# ECG_BTLE.net
KiCad netlist of a schematic drawn in EAGLE
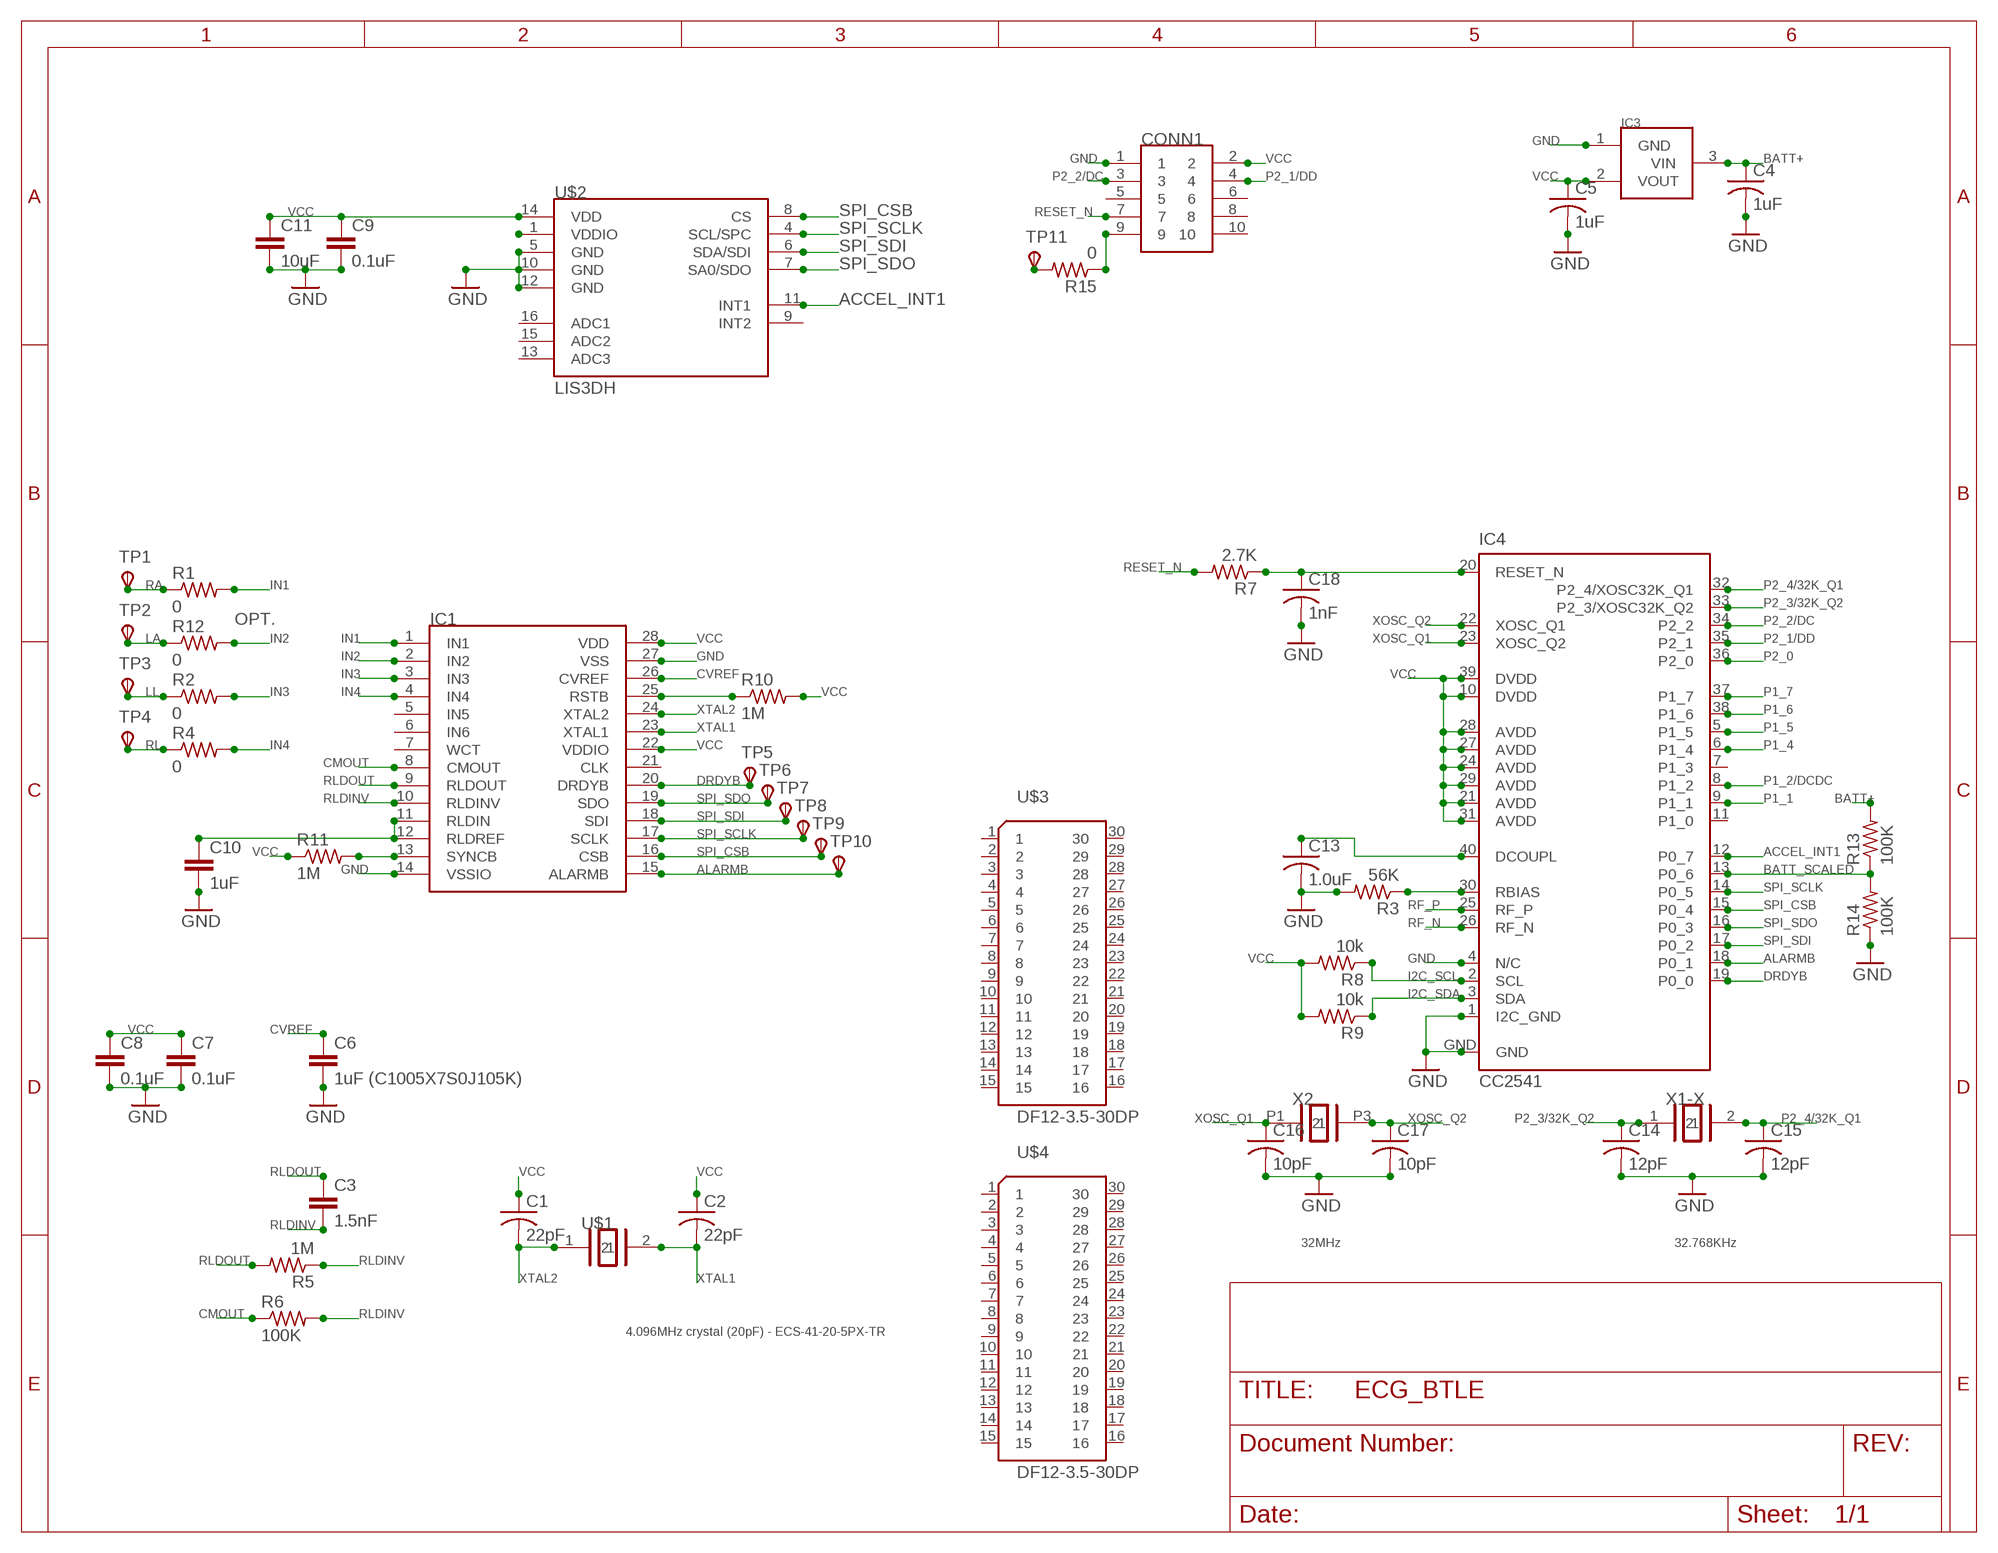
[diagram p0: schematic, sheet 1]

(export (version "E")
  (design (tool "Eeschema 10.0.6"))
  (components
    (comp (ref "C1")
      (value "22pF")
      (footprint "eagle-import:C0201")
      (libsource (lib "eagle-import") (part "C-USC0201"))
    )
    (comp (ref "C2")
      (value "22pF")
      (footprint "eagle-import:C0201")
      (libsource (lib "eagle-import") (part "C-USC0201"))
    )
    (comp (ref "C3")
      (value "1.5nF")
      (footprint "eagle-import:C0402")
      (libsource (lib "eagle-import") (part "C-EUC0402"))
    )
    (comp (ref "C4")
      (value "1uF")
      (footprint "eagle-import:C0201")
      (libsource (lib "eagle-import") (part "C-USC0201"))
    )
    (comp (ref "C5")
      (value "1uF")
      (footprint "eagle-import:C0201")
      (libsource (lib "eagle-import") (part "C-USC0201"))
    )
    (comp (ref "C6")
      (value "1uF (C1005X7S0J105K)")
      (footprint "eagle-import:C0402")
      (libsource (lib "eagle-import") (part "C-EUC0402"))
    )
    (comp (ref "C7")
      (value "0.1uF")
      (footprint "eagle-import:C0402")
      (libsource (lib "eagle-import") (part "C-EUC0402"))
    )
    (comp (ref "C8")
      (value "0.1uF")
      (footprint "eagle-import:C0402")
      (libsource (lib "eagle-import") (part "C-EUC0402"))
    )
    (comp (ref "C9")
      (value "0.1uF")
      (footprint "eagle-import:C0402")
      (libsource (lib "eagle-import") (part "C-EUC0402"))
    )
    (comp (ref "C10")
      (value "1uF")
      (footprint "eagle-import:C0402")
      (libsource (lib "eagle-import") (part "C-EUC0402"))
    )
    (comp (ref "C11")
      (value "10uF")
      (footprint "eagle-import:C0402")
      (libsource (lib "eagle-import") (part "C-EUC0402"))
    )
    (comp (ref "C13")
      (value "1.0uF")
      (footprint "eagle-import:C0402")
      (libsource (lib "eagle-import") (part "C-USC0402"))
    )
    (comp (ref "C14")
      (value "12pF")
      (footprint "eagle-import:C0201")
      (libsource (lib "eagle-import") (part "C-USC0201"))
    )
    (comp (ref "C15")
      (value "12pF")
      (footprint "eagle-import:C0201")
      (libsource (lib "eagle-import") (part "C-USC0201"))
    )
    (comp (ref "C16")
      (value "10pF")
      (footprint "eagle-import:C0201")
      (libsource (lib "eagle-import") (part "C-USC0201"))
    )
    (comp (ref "C17")
      (value "10pF")
      (footprint "eagle-import:C0201")
      (libsource (lib "eagle-import") (part "C-USC0201"))
    )
    (comp (ref "C18")
      (value "1nF")
      (footprint "eagle-import:C0402")
      (libsource (lib "eagle-import") (part "C-USC0402"))
    )
    (comp (ref "CONN1")
      (value "10POS_1.27MM_SMD")
      (footprint "eagle-import:1.27MM_SMD")
      (libsource (lib "eagle-import") (part "10POS_1.27MM_SMD"))
    )
    (comp (ref "IC1")
      (value "ADS1293")
      (footprint "eagle-import:WQFN28")
      (libsource (lib "eagle-import") (part "ADS1293"))
    )
    (comp (ref "IC3")
      (value "MCP1703")
      (footprint "eagle-import:SOT23")
      (libsource (lib "eagle-import") (part "MCP1703"))
    )
    (comp (ref "IC4")
      (value "CC2541")
      (footprint "eagle-import:RHA_S-PVQFN-N40")
      (libsource (lib "eagle-import") (part "CC2541"))
    )
    (comp (ref "R1")
      (value "0")
      (footprint "eagle-import:R0402")
      (libsource (lib "eagle-import") (part "resistor_R-US_R0402"))
    )
    (comp (ref "R2")
      (value "0")
      (footprint "eagle-import:R0402")
      (libsource (lib "eagle-import") (part "resistor_R-US_R0402"))
    )
    (comp (ref "R3")
      (value "56K")
      (footprint "eagle-import:R0201")
      (libsource (lib "eagle-import") (part "R-US_R0201"))
    )
    (comp (ref "R4")
      (value "0")
      (footprint "eagle-import:R0402")
      (libsource (lib "eagle-import") (part "resistor_R-US_R0402"))
    )
    (comp (ref "R5")
      (value "1M")
      (footprint "eagle-import:R0603")
      (libsource (lib "eagle-import") (part "resistor_R-US_R0603"))
    )
    (comp (ref "R6")
      (value "100K")
      (footprint "eagle-import:R0402")
      (libsource (lib "eagle-import") (part "resistor_R-US_R0402"))
    )
    (comp (ref "R7")
      (value "2.7K")
      (footprint "eagle-import:R0201")
      (libsource (lib "eagle-import") (part "R-US_R0201"))
    )
    (comp (ref "R8")
      (value "10k")
      (footprint "eagle-import:R0201")
      (libsource (lib "eagle-import") (part "R-US_R0201"))
    )
    (comp (ref "R9")
      (value "10k")
      (footprint "eagle-import:R0201")
      (libsource (lib "eagle-import") (part "R-US_R0201"))
    )
    (comp (ref "R10")
      (value "1M")
      (footprint "eagle-import:R0402")
      (libsource (lib "eagle-import") (part "resistor_R-US_R0402"))
    )
    (comp (ref "R11")
      (value "1M")
      (footprint "eagle-import:R0402")
      (libsource (lib "eagle-import") (part "resistor_R-US_R0402"))
    )
    (comp (ref "R12")
      (value "0")
      (footprint "eagle-import:R0402")
      (libsource (lib "eagle-import") (part "resistor_R-US_R0402"))
    )
    (comp (ref "R13")
      (value "100K")
      (footprint "eagle-import:R0201")
      (libsource (lib "eagle-import") (part "R-US_R0201"))
    )
    (comp (ref "R14")
      (value "100K")
      (footprint "eagle-import:R0201")
      (libsource (lib "eagle-import") (part "R-US_R0201"))
    )
    (comp (ref "R15")
      (value "0")
      (footprint "eagle-import:R0201")
      (libsource (lib "eagle-import") (part "R-US_R0201"))
    )
    (comp (ref "TP1")
      (value "TPSTP08SQ")
      (footprint "eagle-import:TP08SQ")
      (libsource (lib "eagle-import") (part "TPSTP08SQ"))
    )
    (comp (ref "TP2")
      (value "TPSTP08SQ")
      (footprint "eagle-import:TP08SQ")
      (libsource (lib "eagle-import") (part "TPSTP08SQ"))
    )
    (comp (ref "TP3")
      (value "TPSTP08SQ")
      (footprint "eagle-import:TP08SQ")
      (libsource (lib "eagle-import") (part "TPSTP08SQ"))
    )
    (comp (ref "TP4")
      (value "TPSTP08SQ")
      (footprint "eagle-import:TP08SQ")
      (libsource (lib "eagle-import") (part "TPSTP08SQ"))
    )
    (comp (ref "TP5")
      (value "TPSTP08SQ")
      (footprint "eagle-import:TP08SQ")
      (libsource (lib "eagle-import") (part "TPSTP08SQ"))
    )
    (comp (ref "TP6")
      (value "TPSTP08SQ")
      (footprint "eagle-import:TP08SQ")
      (libsource (lib "eagle-import") (part "TPSTP08SQ"))
    )
    (comp (ref "TP7")
      (value "TPSTP08SQ")
      (footprint "eagle-import:TP08SQ")
      (libsource (lib "eagle-import") (part "TPSTP08SQ"))
    )
    (comp (ref "TP8")
      (value "TPSTP08SQ")
      (footprint "eagle-import:TP08SQ")
      (libsource (lib "eagle-import") (part "TPSTP08SQ"))
    )
    (comp (ref "TP9")
      (value "TPSTP08SQ")
      (footprint "eagle-import:TP08SQ")
      (libsource (lib "eagle-import") (part "TPSTP08SQ"))
    )
    (comp (ref "TP10")
      (value "TPSTP08SQ")
      (footprint "eagle-import:TP08SQ")
      (libsource (lib "eagle-import") (part "TPSTP08SQ"))
    )
    (comp (ref "TP11")
      (value "TPSTP08SQ")
      (footprint "eagle-import:TP08SQ")
      (libsource (lib "eagle-import") (part "TPSTP08SQ"))
    )
    (comp (ref "U$1")
      (value "XTAL-CSM7")
      (footprint "eagle-import:CSM-7")
      (libsource (lib "eagle-import") (part "XTAL-CSM7"))
    )
    (comp (ref "U$2")
      (value "LIS3DH")
      (footprint "eagle-import:LGA16-3MM")
      (libsource (lib "eagle-import") (part "LIS3DH"))
    )
    (comp (ref "U$3")
      (value "DF12-3.5-30DP")
      (footprint "eagle-import:DF12-3.5-30DP")
      (libsource (lib "eagle-import") (part "DF12-3.5-30DP"))
    )
    (comp (ref "U$4")
      (value "DF12-3.5-30DP")
      (footprint "eagle-import:DF12-3.5-30DP")
      (libsource (lib "eagle-import") (part "DF12-3.5-30DP"))
    )
    (comp (ref "X1-X")
      (value "XTAL-2SMD")
      (footprint "eagle-import:2-SMD")
      (libsource (lib "eagle-import") (part "XTAL-2SMD"))
    )
    (comp (ref "X2")
      (value "XTAL_403")
      (footprint "eagle-import:4-SMD")
      (libsource (lib "eagle-import") (part "XTAL_403"))
    )
  )
  (nets
    (net (code "1") (name "/ACCEL_INT1") (class "Default")
      (node (ref "IC4") (pin "12") (pinfunction "P0_7_12") (pintype "bidirectional"))
      (node (ref "U$2") (pin "11") (pinfunction "INT1_11") (pintype "bidirectional"))
    )
    (net (code "2") (name "/ALARMB") (class "Default")
      (node (ref "IC1") (pin "15") (pinfunction "ALARMB_15") (pintype "bidirectional"))
      (node (ref "IC4") (pin "18") (pinfunction "P0_1_18") (pintype "bidirectional"))
      (node (ref "TP10") (pin "TP") (pinfunction "PP_TP") (pintype "input"))
    )
    (net (code "3") (name "/BATT+") (class "Default")
      (node (ref "C4") (pin "1") (pinfunction "1_1") (pintype "passive"))
      (node (ref "IC3") (pin "3") (pinfunction "VIN_3") (pintype "bidirectional"))
      (node (ref "R13") (pin "2") (pinfunction "2_2") (pintype "passive"))
    )
    (net (code "4") (name "/BATT_SCALED") (class "Default")
      (node (ref "IC4") (pin "13") (pinfunction "P0_6_13") (pintype "bidirectional"))
      (node (ref "R13") (pin "1") (pinfunction "1_1") (pintype "passive"))
      (node (ref "R14") (pin "2") (pinfunction "2_2") (pintype "passive"))
    )
    (net (code "5") (name "/CMOUT") (class "Default")
      (node (ref "IC1") (pin "8") (pinfunction "CMOUT_8") (pintype "bidirectional"))
      (node (ref "R6") (pin "1") (pinfunction "1_1") (pintype "passive"))
    )
    (net (code "6") (name "/CVREF") (class "Default")
      (node (ref "C6") (pin "1") (pinfunction "1_1") (pintype "passive"))
      (node (ref "IC1") (pin "26") (pinfunction "CVREF_26") (pintype "bidirectional"))
    )
    (net (code "7") (name "/DRDYB") (class "Default")
      (node (ref "IC1") (pin "20") (pinfunction "DRDYB_20") (pintype "bidirectional"))
      (node (ref "IC4") (pin "19") (pinfunction "P0_0_19") (pintype "bidirectional"))
      (node (ref "TP5") (pin "TP") (pinfunction "PP_TP") (pintype "input"))
    )
    (net (code "8") (name "/I2C_SCL") (class "Default")
      (node (ref "IC4") (pin "2") (pinfunction "SCL_2") (pintype "bidirectional"))
      (node (ref "R8") (pin "1") (pinfunction "1_1") (pintype "passive"))
    )
    (net (code "9") (name "/I2C_SDA") (class "Default")
      (node (ref "IC4") (pin "3") (pinfunction "SDA_3") (pintype "bidirectional"))
      (node (ref "R9") (pin "1") (pinfunction "1_1") (pintype "passive"))
    )
    (net (code "10") (name "/IN1") (class "Default")
      (node (ref "IC1") (pin "1") (pinfunction "IN1_1") (pintype "bidirectional"))
      (node (ref "R1") (pin "2") (pinfunction "2_2") (pintype "passive"))
    )
    (net (code "11") (name "/IN2") (class "Default")
      (node (ref "IC1") (pin "2") (pinfunction "IN2_2") (pintype "bidirectional"))
      (node (ref "R12") (pin "2") (pinfunction "2_2") (pintype "passive"))
    )
    (net (code "12") (name "/IN3") (class "Default")
      (node (ref "IC1") (pin "3") (pinfunction "IN3_3") (pintype "bidirectional"))
      (node (ref "R2") (pin "2") (pinfunction "2_2") (pintype "passive"))
    )
    (net (code "13") (name "/IN4") (class "Default")
      (node (ref "IC1") (pin "4") (pinfunction "IN4_4") (pintype "bidirectional"))
      (node (ref "R4") (pin "2") (pinfunction "2_2") (pintype "passive"))
    )
    (net (code "14") (name "/LA") (class "Default")
      (node (ref "R12") (pin "1") (pinfunction "1_1") (pintype "passive"))
      (node (ref "TP2") (pin "TP") (pinfunction "PP_TP") (pintype "input"))
    )
    (net (code "15") (name "/LL") (class "Default")
      (node (ref "R2") (pin "1") (pinfunction "1_1") (pintype "passive"))
      (node (ref "TP3") (pin "TP") (pinfunction "PP_TP") (pintype "input"))
    )
    (net (code "16") (name "/P1_1") (class "Default")
      (node (ref "IC4") (pin "9") (pinfunction "P1_1_9") (pintype "bidirectional"))
    )
    (net (code "17") (name "/P1_2{slash}DCDC") (class "Default")
      (node (ref "IC4") (pin "8") (pinfunction "P1_2_8") (pintype "bidirectional"))
    )
    (net (code "18") (name "/P1_4") (class "Default")
      (node (ref "IC4") (pin "6") (pinfunction "P1_4_6") (pintype "bidirectional"))
    )
    (net (code "19") (name "/P1_5") (class "Default")
      (node (ref "IC4") (pin "5") (pinfunction "P1_5_5") (pintype "bidirectional"))
    )
    (net (code "20") (name "/P1_6") (class "Default")
      (node (ref "IC4") (pin "38") (pinfunction "P1_6_38") (pintype "bidirectional"))
    )
    (net (code "21") (name "/P1_7") (class "Default")
      (node (ref "IC4") (pin "37") (pinfunction "P1_7_37") (pintype "bidirectional"))
    )
    (net (code "22") (name "/P2_0") (class "Default")
      (node (ref "IC4") (pin "36") (pinfunction "P2_0_36") (pintype "bidirectional"))
    )
    (net (code "23") (name "/P2_1{slash}DD") (class "Default")
      (node (ref "CONN1") (pin "4") (pinfunction "4_4") (pintype "bidirectional"))
      (node (ref "IC4") (pin "35") (pinfunction "P2_1_35") (pintype "bidirectional"))
    )
    (net (code "24") (name "/P2_2{slash}DC") (class "Default")
      (node (ref "CONN1") (pin "3") (pinfunction "3_3") (pintype "bidirectional"))
      (node (ref "IC4") (pin "34") (pinfunction "P2_2_34") (pintype "bidirectional"))
    )
    (net (code "25") (name "/P2_3{slash}32K_Q2") (class "Default")
      (node (ref "C14") (pin "1") (pinfunction "1_1") (pintype "passive"))
      (node (ref "IC4") (pin "33") (pinfunction "P2_3/XOSC32K_Q2_33") (pintype "bidirectional"))
      (node (ref "X1-X") (pin "1") (pinfunction "1_1") (pintype "bidirectional"))
    )
    (net (code "26") (name "/P2_4{slash}32K_Q1") (class "Default")
      (node (ref "C15") (pin "1") (pinfunction "1_1") (pintype "passive"))
      (node (ref "IC4") (pin "32") (pinfunction "P2_4/XOSC32K_Q1_32") (pintype "bidirectional"))
      (node (ref "X1-X") (pin "2") (pinfunction "2_2") (pintype "bidirectional"))
    )
    (net (code "27") (name "/RA") (class "Default")
      (node (ref "R1") (pin "1") (pinfunction "1_1") (pintype "passive"))
      (node (ref "TP1") (pin "TP") (pinfunction "PP_TP") (pintype "input"))
    )
    (net (code "28") (name "/RESET_N") (class "Default")
      (node (ref "CONN1") (pin "7") (pinfunction "7_7") (pintype "bidirectional"))
      (node (ref "R7") (pin "2") (pinfunction "2_2") (pintype "passive"))
    )
    (net (code "29") (name "/RF_N") (class "Default")
      (node (ref "IC4") (pin "26") (pinfunction "RF_N_26") (pintype "bidirectional"))
    )
    (net (code "30") (name "/RF_P") (class "Default")
      (node (ref "IC4") (pin "25") (pinfunction "RF_P_25") (pintype "bidirectional"))
    )
    (net (code "31") (name "/RL") (class "Default")
      (node (ref "R4") (pin "1") (pinfunction "1_1") (pintype "passive"))
      (node (ref "TP4") (pin "TP") (pinfunction "PP_TP") (pintype "input"))
    )
    (net (code "32") (name "/RLDINV") (class "Default")
      (node (ref "C3") (pin "2") (pinfunction "2_2") (pintype "passive"))
      (node (ref "IC1") (pin "10") (pinfunction "RLDINV_10") (pintype "bidirectional"))
      (node (ref "R5") (pin "1") (pinfunction "1_1") (pintype "passive"))
      (node (ref "R6") (pin "2") (pinfunction "2_2") (pintype "passive"))
    )
    (net (code "33") (name "/RLDOUT") (class "Default")
      (node (ref "C3") (pin "1") (pinfunction "1_1") (pintype "passive"))
      (node (ref "IC1") (pin "9") (pinfunction "RLDOUT_9") (pintype "bidirectional"))
      (node (ref "R5") (pin "2") (pinfunction "2_2") (pintype "passive"))
    )
    (net (code "34") (name "/SPI_CSB") (class "Default")
      (node (ref "IC1") (pin "16") (pinfunction "CSB_16") (pintype "bidirectional"))
      (node (ref "IC4") (pin "15") (pinfunction "P0_4_15") (pintype "bidirectional"))
      (node (ref "TP9") (pin "TP") (pinfunction "PP_TP") (pintype "input"))
      (node (ref "U$2") (pin "8") (pinfunction "CS_8") (pintype "bidirectional"))
    )
    (net (code "35") (name "/SPI_SCLK") (class "Default")
      (node (ref "IC1") (pin "17") (pinfunction "SCLK_17") (pintype "bidirectional"))
      (node (ref "IC4") (pin "14") (pinfunction "P0_5_14") (pintype "bidirectional"))
      (node (ref "TP8") (pin "TP") (pinfunction "PP_TP") (pintype "input"))
      (node (ref "U$2") (pin "4") (pinfunction "SCL/SPC_4") (pintype "bidirectional"))
    )
    (net (code "36") (name "/SPI_SDI") (class "Default")
      (node (ref "IC1") (pin "18") (pinfunction "SDI_18") (pintype "bidirectional"))
      (node (ref "IC4") (pin "17") (pinfunction "P0_2_17") (pintype "bidirectional"))
      (node (ref "TP7") (pin "TP") (pinfunction "PP_TP") (pintype "input"))
      (node (ref "U$2") (pin "6") (pinfunction "SDA/SDI_6") (pintype "bidirectional"))
    )
    (net (code "37") (name "/SPI_SDO") (class "Default")
      (node (ref "IC1") (pin "19") (pinfunction "SDO_19") (pintype "bidirectional"))
      (node (ref "IC4") (pin "16") (pinfunction "P0_3_16") (pintype "bidirectional"))
      (node (ref "TP6") (pin "TP") (pinfunction "PP_TP") (pintype "input"))
      (node (ref "U$2") (pin "7") (pinfunction "SA0/SDO_7") (pintype "bidirectional"))
    )
    (net (code "38") (name "/VCC") (class "Default")
      (node (ref "C1") (pin "1") (pinfunction "1_1") (pintype "passive"))
      (node (ref "C11") (pin "1") (pinfunction "1_1") (pintype "passive"))
      (node (ref "C2") (pin "1") (pinfunction "1_1") (pintype "passive"))
      (node (ref "C5") (pin "1") (pinfunction "1_1") (pintype "passive"))
      (node (ref "C7") (pin "1") (pinfunction "1_1") (pintype "passive"))
      (node (ref "C8") (pin "1") (pinfunction "1_1") (pintype "passive"))
      (node (ref "C9") (pin "1") (pinfunction "1_1") (pintype "passive"))
      (node (ref "CONN1") (pin "2") (pinfunction "2_2") (pintype "bidirectional"))
      (node (ref "IC1") (pin "22") (pinfunction "VDDIO_22") (pintype "bidirectional"))
      (node (ref "IC1") (pin "28") (pinfunction "VDD_28") (pintype "bidirectional"))
      (node (ref "IC3") (pin "2") (pinfunction "VOUT_2") (pintype "bidirectional"))
      (node (ref "IC4") (pin "10") (pinfunction "DVDD_10") (pintype "power_in"))
      (node (ref "IC4") (pin "21") (pinfunction "AVDD_21") (pintype "power_in"))
      (node (ref "IC4") (pin "24") (pinfunction "AVDD_24") (pintype "power_in"))
      (node (ref "IC4") (pin "27") (pinfunction "AVDD_27") (pintype "power_in"))
      (node (ref "IC4") (pin "28") (pinfunction "AVDD_28") (pintype "power_in"))
      (node (ref "IC4") (pin "29") (pinfunction "AVDD_29") (pintype "power_in"))
      (node (ref "IC4") (pin "31") (pinfunction "AVDD_31") (pintype "power_in"))
      (node (ref "IC4") (pin "39") (pinfunction "DVDD_39") (pintype "power_in"))
      (node (ref "R10") (pin "2") (pinfunction "2_2") (pintype "passive"))
      (node (ref "R11") (pin "1") (pinfunction "1_1") (pintype "passive"))
      (node (ref "R8") (pin "2") (pinfunction "2_2") (pintype "passive"))
      (node (ref "R9") (pin "2") (pinfunction "2_2") (pintype "passive"))
      (node (ref "U$2") (pin "14") (pinfunction "VDD_14") (pintype "bidirectional"))
    )
    (net (code "39") (name "/XOSC_Q1") (class "Default")
      (node (ref "C16") (pin "1") (pinfunction "1_1") (pintype "passive"))
      (node (ref "IC4") (pin "23") (pinfunction "XOSC_Q2_23") (pintype "bidirectional"))
      (node (ref "X2") (pin "P1") (pinfunction "1_P1") (pintype "bidirectional"))
    )
    (net (code "40") (name "/XOSC_Q2") (class "Default")
      (node (ref "C17") (pin "1") (pinfunction "1_1") (pintype "passive"))
      (node (ref "IC4") (pin "22") (pinfunction "XOSC_Q1_22") (pintype "bidirectional"))
      (node (ref "X2") (pin "P3") (pinfunction "2_P3") (pintype "bidirectional"))
    )
    (net (code "41") (name "/XTAL1") (class "Default")
      (node (ref "C2") (pin "2") (pinfunction "2_2") (pintype "passive"))
      (node (ref "IC1") (pin "23") (pinfunction "XTAL1_23") (pintype "bidirectional"))
      (node (ref "U$1") (pin "2") (pinfunction "2_2") (pintype "bidirectional"))
    )
    (net (code "42") (name "/XTAL2") (class "Default")
      (node (ref "C1") (pin "2") (pinfunction "2_2") (pintype "passive"))
      (node (ref "IC1") (pin "24") (pinfunction "XTAL2_24") (pintype "bidirectional"))
      (node (ref "U$1") (pin "1") (pinfunction "1_1") (pintype "bidirectional"))
    )
    (net (code "43") (name "GND") (class "Default")
      (node (ref "C10") (pin "2") (pinfunction "2_2") (pintype "passive"))
      (node (ref "C11") (pin "2") (pinfunction "2_2") (pintype "passive"))
      (node (ref "C13") (pin "2") (pinfunction "2_2") (pintype "passive"))
      (node (ref "C14") (pin "2") (pinfunction "2_2") (pintype "passive"))
      (node (ref "C15") (pin "2") (pinfunction "2_2") (pintype "passive"))
      (node (ref "C16") (pin "2") (pinfunction "2_2") (pintype "passive"))
      (node (ref "C17") (pin "2") (pinfunction "2_2") (pintype "passive"))
      (node (ref "C18") (pin "2") (pinfunction "2_2") (pintype "passive"))
      (node (ref "C4") (pin "2") (pinfunction "2_2") (pintype "passive"))
      (node (ref "C5") (pin "2") (pinfunction "2_2") (pintype "passive"))
      (node (ref "C6") (pin "2") (pinfunction "2_2") (pintype "passive"))
      (node (ref "C7") (pin "2") (pinfunction "2_2") (pintype "passive"))
      (node (ref "C8") (pin "2") (pinfunction "2_2") (pintype "passive"))
      (node (ref "C9") (pin "2") (pinfunction "2_2") (pintype "passive"))
      (node (ref "CONN1") (pin "1") (pinfunction "1_1") (pintype "bidirectional"))
      (node (ref "IC1") (pin "14") (pinfunction "VSSIO_14") (pintype "bidirectional"))
      (node (ref "IC1") (pin "27") (pinfunction "VSS_27") (pintype "bidirectional"))
      (node (ref "IC3") (pin "1") (pinfunction "GND_1") (pintype "bidirectional"))
      (node (ref "IC4") (pin "1") (pinfunction "I2C_GND_1") (pintype "power_in"))
      (node (ref "IC4") (pin "4") (pinfunction "N/C_4") (pintype "power_in"))
      (node (ref "IC4") (pin "GND") (pinfunction "GND_GND") (pintype "passive"))
      (node (ref "R14") (pin "1") (pinfunction "1_1") (pintype "passive"))
      (node (ref "R3") (pin "2") (pinfunction "2_2") (pintype "passive"))
      (node (ref "U$2") (pin "10") (pinfunction "GND_10") (pintype "bidirectional"))
      (node (ref "U$2") (pin "12") (pinfunction "GND_12") (pintype "bidirectional"))
      (node (ref "U$2") (pin "5") (pinfunction "GND_5") (pintype "bidirectional"))
    )
    (net (code "44") (name "Net-(CONN1-Pad9)") (class "Default")
      (node (ref "CONN1") (pin "9") (pinfunction "9_9") (pintype "bidirectional"))
      (node (ref "R15") (pin "1") (pinfunction "1_1") (pintype "passive"))
    )
    (net (code "45") (name "Net-(IC1-RLDIN)") (class "Default")
      (node (ref "C10") (pin "1") (pinfunction "1_1") (pintype "passive"))
      (node (ref "IC1") (pin "11") (pinfunction "RLDIN_11") (pintype "bidirectional"))
      (node (ref "IC1") (pin "12") (pinfunction "RLDREF_12") (pintype "bidirectional"))
    )
    (net (code "46") (name "Net-(IC1-RSTB)") (class "Default")
      (node (ref "IC1") (pin "25") (pinfunction "RSTB_25") (pintype "bidirectional"))
      (node (ref "R10") (pin "1") (pinfunction "1_1") (pintype "passive"))
    )
    (net (code "47") (name "Net-(IC1-SYNCB)") (class "Default")
      (node (ref "IC1") (pin "13") (pinfunction "SYNCB_13") (pintype "bidirectional"))
      (node (ref "R11") (pin "2") (pinfunction "2_2") (pintype "passive"))
    )
    (net (code "48") (name "Net-(IC4-DCOUPL)") (class "Default")
      (node (ref "C13") (pin "1") (pinfunction "1_1") (pintype "passive"))
      (node (ref "IC4") (pin "40") (pinfunction "DCOUPL_40") (pintype "power_in"))
    )
    (net (code "49") (name "Net-(IC4-RBIAS)") (class "Default")
      (node (ref "IC4") (pin "30") (pinfunction "RBIAS_30") (pintype "bidirectional"))
      (node (ref "R3") (pin "1") (pinfunction "1_1") (pintype "passive"))
    )
    (net (code "50") (name "Net-(IC4-RESET_N)") (class "Default")
      (node (ref "C18") (pin "1") (pinfunction "1_1") (pintype "passive"))
      (node (ref "IC4") (pin "20") (pinfunction "RESET_N_20") (pintype "input"))
      (node (ref "R7") (pin "1") (pinfunction "1_1") (pintype "passive"))
    )
    (net (code "51") (name "Net-(TP11-PP)") (class "Default")
      (node (ref "R15") (pin "2") (pinfunction "2_2") (pintype "passive"))
      (node (ref "TP11") (pin "TP") (pinfunction "PP_TP") (pintype "input"))
    )
    (net (code "52") (name "unconnected-(CONN1-Pad5)") (class "Default")
      (node (ref "CONN1") (pin "5") (pinfunction "5_5") (pintype "bidirectional"))
    )
    (net (code "53") (name "unconnected-(CONN1-Pad6)") (class "Default")
      (node (ref "CONN1") (pin "6") (pinfunction "6_6") (pintype "bidirectional"))
    )
    (net (code "54") (name "unconnected-(CONN1-Pad8)") (class "Default")
      (node (ref "CONN1") (pin "8") (pinfunction "8_8") (pintype "bidirectional"))
    )
    (net (code "55") (name "unconnected-(CONN1-Pad10)") (class "Default")
      (node (ref "CONN1") (pin "10") (pinfunction "10_10") (pintype "bidirectional"))
    )
    (net (code "56") (name "unconnected-(IC1-CLK-Pad21)") (class "Default")
      (node (ref "IC1") (pin "21") (pinfunction "CLK_21") (pintype "bidirectional"))
    )
    (net (code "57") (name "unconnected-(IC1-IN5-Pad5)") (class "Default")
      (node (ref "IC1") (pin "5") (pinfunction "IN5_5") (pintype "bidirectional"))
    )
    (net (code "58") (name "unconnected-(IC1-IN6-Pad6)") (class "Default")
      (node (ref "IC1") (pin "6") (pinfunction "IN6_6") (pintype "bidirectional"))
    )
    (net (code "59") (name "unconnected-(IC1-WCT-Pad7)") (class "Default")
      (node (ref "IC1") (pin "7") (pinfunction "WCT_7") (pintype "bidirectional"))
    )
    (net (code "60") (name "unconnected-(IC4-P1_0-Pad11)") (class "Default")
      (node (ref "IC4") (pin "11") (pinfunction "P1_0_11") (pintype "bidirectional"))
    )
    (net (code "61") (name "unconnected-(IC4-P1_3-Pad7)") (class "Default")
      (node (ref "IC4") (pin "7") (pinfunction "P1_3_7") (pintype "bidirectional"))
    )
    (net (code "62") (name "unconnected-(U$2-ADC1-Pad16)") (class "Default")
      (node (ref "U$2") (pin "16") (pinfunction "ADC1_16") (pintype "bidirectional"))
    )
    (net (code "63") (name "unconnected-(U$2-ADC2-Pad15)") (class "Default")
      (node (ref "U$2") (pin "15") (pinfunction "ADC2_15") (pintype "bidirectional"))
    )
    (net (code "64") (name "unconnected-(U$2-ADC3-Pad13)") (class "Default")
      (node (ref "U$2") (pin "13") (pinfunction "ADC3_13") (pintype "bidirectional"))
    )
    (net (code "65") (name "unconnected-(U$2-INT2-Pad9)") (class "Default")
      (node (ref "U$2") (pin "9") (pinfunction "INT2_9") (pintype "bidirectional"))
    )
    (net (code "66") (name "unconnected-(U$2-VDDIO-Pad1)") (class "Default")
      (node (ref "U$2") (pin "1") (pinfunction "VDDIO_1") (pintype "bidirectional"))
    )
    (net (code "67") (name "unconnected-(U$3-Pad1)") (class "Default")
      (node (ref "U$3") (pin "1") (pinfunction "1_1") (pintype "bidirectional"))
    )
    (net (code "68") (name "unconnected-(U$3-Pad2)") (class "Default")
      (node (ref "U$3") (pin "2") (pinfunction "2_2") (pintype "bidirectional"))
    )
    (net (code "69") (name "unconnected-(U$3-Pad3)") (class "Default")
      (node (ref "U$3") (pin "3") (pinfunction "3_3") (pintype "bidirectional"))
    )
    (net (code "70") (name "unconnected-(U$3-Pad4)") (class "Default")
      (node (ref "U$3") (pin "4") (pinfunction "4_4") (pintype "bidirectional"))
    )
    (net (code "71") (name "unconnected-(U$3-Pad5)") (class "Default")
      (node (ref "U$3") (pin "5") (pinfunction "5_5") (pintype "bidirectional"))
    )
    (net (code "72") (name "unconnected-(U$3-Pad6)") (class "Default")
      (node (ref "U$3") (pin "6") (pinfunction "6_6") (pintype "bidirectional"))
    )
    (net (code "73") (name "unconnected-(U$3-Pad7)") (class "Default")
      (node (ref "U$3") (pin "7") (pinfunction "7_7") (pintype "bidirectional"))
    )
    (net (code "74") (name "unconnected-(U$3-Pad8)") (class "Default")
      (node (ref "U$3") (pin "8") (pinfunction "8_8") (pintype "bidirectional"))
    )
    (net (code "75") (name "unconnected-(U$3-Pad9)") (class "Default")
      (node (ref "U$3") (pin "9") (pinfunction "9_9") (pintype "bidirectional"))
    )
    (net (code "76") (name "unconnected-(U$3-Pad10)") (class "Default")
      (node (ref "U$3") (pin "10") (pinfunction "10_10") (pintype "bidirectional"))
    )
    (net (code "77") (name "unconnected-(U$3-Pad11)") (class "Default")
      (node (ref "U$3") (pin "11") (pinfunction "11_11") (pintype "bidirectional"))
    )
    (net (code "78") (name "unconnected-(U$3-Pad12)") (class "Default")
      (node (ref "U$3") (pin "12") (pinfunction "12_12") (pintype "bidirectional"))
    )
    (net (code "79") (name "unconnected-(U$3-Pad13)") (class "Default")
      (node (ref "U$3") (pin "13") (pinfunction "13_13") (pintype "bidirectional"))
    )
    (net (code "80") (name "unconnected-(U$3-Pad14)") (class "Default")
      (node (ref "U$3") (pin "14") (pinfunction "14_14") (pintype "bidirectional"))
    )
    (net (code "81") (name "unconnected-(U$3-Pad15)") (class "Default")
      (node (ref "U$3") (pin "15") (pinfunction "15_15") (pintype "bidirectional"))
    )
    (net (code "82") (name "unconnected-(U$3-Pad16)") (class "Default")
      (node (ref "U$3") (pin "16") (pinfunction "16_16") (pintype "bidirectional"))
    )
    (net (code "83") (name "unconnected-(U$3-Pad17)") (class "Default")
      (node (ref "U$3") (pin "17") (pinfunction "17_17") (pintype "bidirectional"))
    )
    (net (code "84") (name "unconnected-(U$3-Pad18)") (class "Default")
      (node (ref "U$3") (pin "18") (pinfunction "18_18") (pintype "bidirectional"))
    )
    (net (code "85") (name "unconnected-(U$3-Pad19)") (class "Default")
      (node (ref "U$3") (pin "19") (pinfunction "19_19") (pintype "bidirectional"))
    )
    (net (code "86") (name "unconnected-(U$3-Pad20)") (class "Default")
      (node (ref "U$3") (pin "20") (pinfunction "20_20") (pintype "bidirectional"))
    )
    (net (code "87") (name "unconnected-(U$3-Pad21)") (class "Default")
      (node (ref "U$3") (pin "21") (pinfunction "21_21") (pintype "bidirectional"))
    )
    (net (code "88") (name "unconnected-(U$3-Pad22)") (class "Default")
      (node (ref "U$3") (pin "22") (pinfunction "22_22") (pintype "bidirectional"))
    )
    (net (code "89") (name "unconnected-(U$3-Pad23)") (class "Default")
      (node (ref "U$3") (pin "23") (pinfunction "23_23") (pintype "bidirectional"))
    )
    (net (code "90") (name "unconnected-(U$3-Pad24)") (class "Default")
      (node (ref "U$3") (pin "24") (pinfunction "24_24") (pintype "bidirectional"))
    )
    (net (code "91") (name "unconnected-(U$3-Pad25)") (class "Default")
      (node (ref "U$3") (pin "25") (pinfunction "25_25") (pintype "bidirectional"))
    )
    (net (code "92") (name "unconnected-(U$3-Pad26)") (class "Default")
      (node (ref "U$3") (pin "26") (pinfunction "26_26") (pintype "bidirectional"))
    )
    (net (code "93") (name "unconnected-(U$3-Pad27)") (class "Default")
      (node (ref "U$3") (pin "27") (pinfunction "27_27") (pintype "bidirectional"))
    )
    (net (code "94") (name "unconnected-(U$3-Pad28)") (class "Default")
      (node (ref "U$3") (pin "28") (pinfunction "28_28") (pintype "bidirectional"))
    )
    (net (code "95") (name "unconnected-(U$3-Pad29)") (class "Default")
      (node (ref "U$3") (pin "29") (pinfunction "29_29") (pintype "bidirectional"))
    )
    (net (code "96") (name "unconnected-(U$3-Pad30)") (class "Default")
      (node (ref "U$3") (pin "30") (pinfunction "30_30") (pintype "bidirectional"))
    )
    (net (code "97") (name "unconnected-(U$4-Pad1)") (class "Default")
      (node (ref "U$4") (pin "1") (pinfunction "1_1") (pintype "bidirectional"))
    )
    (net (code "98") (name "unconnected-(U$4-Pad2)") (class "Default")
      (node (ref "U$4") (pin "2") (pinfunction "2_2") (pintype "bidirectional"))
    )
    (net (code "99") (name "unconnected-(U$4-Pad3)") (class "Default")
      (node (ref "U$4") (pin "3") (pinfunction "3_3") (pintype "bidirectional"))
    )
    (net (code "100") (name "unconnected-(U$4-Pad4)") (class "Default")
      (node (ref "U$4") (pin "4") (pinfunction "4_4") (pintype "bidirectional"))
    )
    (net (code "101") (name "unconnected-(U$4-Pad5)") (class "Default")
      (node (ref "U$4") (pin "5") (pinfunction "5_5") (pintype "bidirectional"))
    )
    (net (code "102") (name "unconnected-(U$4-Pad6)") (class "Default")
      (node (ref "U$4") (pin "6") (pinfunction "6_6") (pintype "bidirectional"))
    )
    (net (code "103") (name "unconnected-(U$4-Pad7)") (class "Default")
      (node (ref "U$4") (pin "7") (pinfunction "7_7") (pintype "bidirectional"))
    )
    (net (code "104") (name "unconnected-(U$4-Pad8)") (class "Default")
      (node (ref "U$4") (pin "8") (pinfunction "8_8") (pintype "bidirectional"))
    )
    (net (code "105") (name "unconnected-(U$4-Pad9)") (class "Default")
      (node (ref "U$4") (pin "9") (pinfunction "9_9") (pintype "bidirectional"))
    )
    (net (code "106") (name "unconnected-(U$4-Pad10)") (class "Default")
      (node (ref "U$4") (pin "10") (pinfunction "10_10") (pintype "bidirectional"))
    )
    (net (code "107") (name "unconnected-(U$4-Pad11)") (class "Default")
      (node (ref "U$4") (pin "11") (pinfunction "11_11") (pintype "bidirectional"))
    )
    (net (code "108") (name "unconnected-(U$4-Pad12)") (class "Default")
      (node (ref "U$4") (pin "12") (pinfunction "12_12") (pintype "bidirectional"))
    )
    (net (code "109") (name "unconnected-(U$4-Pad13)") (class "Default")
      (node (ref "U$4") (pin "13") (pinfunction "13_13") (pintype "bidirectional"))
    )
    (net (code "110") (name "unconnected-(U$4-Pad14)") (class "Default")
      (node (ref "U$4") (pin "14") (pinfunction "14_14") (pintype "bidirectional"))
    )
    (net (code "111") (name "unconnected-(U$4-Pad15)") (class "Default")
      (node (ref "U$4") (pin "15") (pinfunction "15_15") (pintype "bidirectional"))
    )
    (net (code "112") (name "unconnected-(U$4-Pad16)") (class "Default")
      (node (ref "U$4") (pin "16") (pinfunction "16_16") (pintype "bidirectional"))
    )
    (net (code "113") (name "unconnected-(U$4-Pad17)") (class "Default")
      (node (ref "U$4") (pin "17") (pinfunction "17_17") (pintype "bidirectional"))
    )
    (net (code "114") (name "unconnected-(U$4-Pad18)") (class "Default")
      (node (ref "U$4") (pin "18") (pinfunction "18_18") (pintype "bidirectional"))
    )
    (net (code "115") (name "unconnected-(U$4-Pad19)") (class "Default")
      (node (ref "U$4") (pin "19") (pinfunction "19_19") (pintype "bidirectional"))
    )
    (net (code "116") (name "unconnected-(U$4-Pad20)") (class "Default")
      (node (ref "U$4") (pin "20") (pinfunction "20_20") (pintype "bidirectional"))
    )
    (net (code "117") (name "unconnected-(U$4-Pad21)") (class "Default")
      (node (ref "U$4") (pin "21") (pinfunction "21_21") (pintype "bidirectional"))
    )
    (net (code "118") (name "unconnected-(U$4-Pad22)") (class "Default")
      (node (ref "U$4") (pin "22") (pinfunction "22_22") (pintype "bidirectional"))
    )
    (net (code "119") (name "unconnected-(U$4-Pad23)") (class "Default")
      (node (ref "U$4") (pin "23") (pinfunction "23_23") (pintype "bidirectional"))
    )
    (net (code "120") (name "unconnected-(U$4-Pad24)") (class "Default")
      (node (ref "U$4") (pin "24") (pinfunction "24_24") (pintype "bidirectional"))
    )
    (net (code "121") (name "unconnected-(U$4-Pad25)") (class "Default")
      (node (ref "U$4") (pin "25") (pinfunction "25_25") (pintype "bidirectional"))
    )
    (net (code "122") (name "unconnected-(U$4-Pad26)") (class "Default")
      (node (ref "U$4") (pin "26") (pinfunction "26_26") (pintype "bidirectional"))
    )
    (net (code "123") (name "unconnected-(U$4-Pad27)") (class "Default")
      (node (ref "U$4") (pin "27") (pinfunction "27_27") (pintype "bidirectional"))
    )
    (net (code "124") (name "unconnected-(U$4-Pad28)") (class "Default")
      (node (ref "U$4") (pin "28") (pinfunction "28_28") (pintype "bidirectional"))
    )
    (net (code "125") (name "unconnected-(U$4-Pad29)") (class "Default")
      (node (ref "U$4") (pin "29") (pinfunction "29_29") (pintype "bidirectional"))
    )
    (net (code "126") (name "unconnected-(U$4-Pad30)") (class "Default")
      (node (ref "U$4") (pin "30") (pinfunction "30_30") (pintype "bidirectional"))
    )
  )
)
